# Relay_Board_1st_Iteration.net
KiCad netlist of a schematic drawn in EAGLE
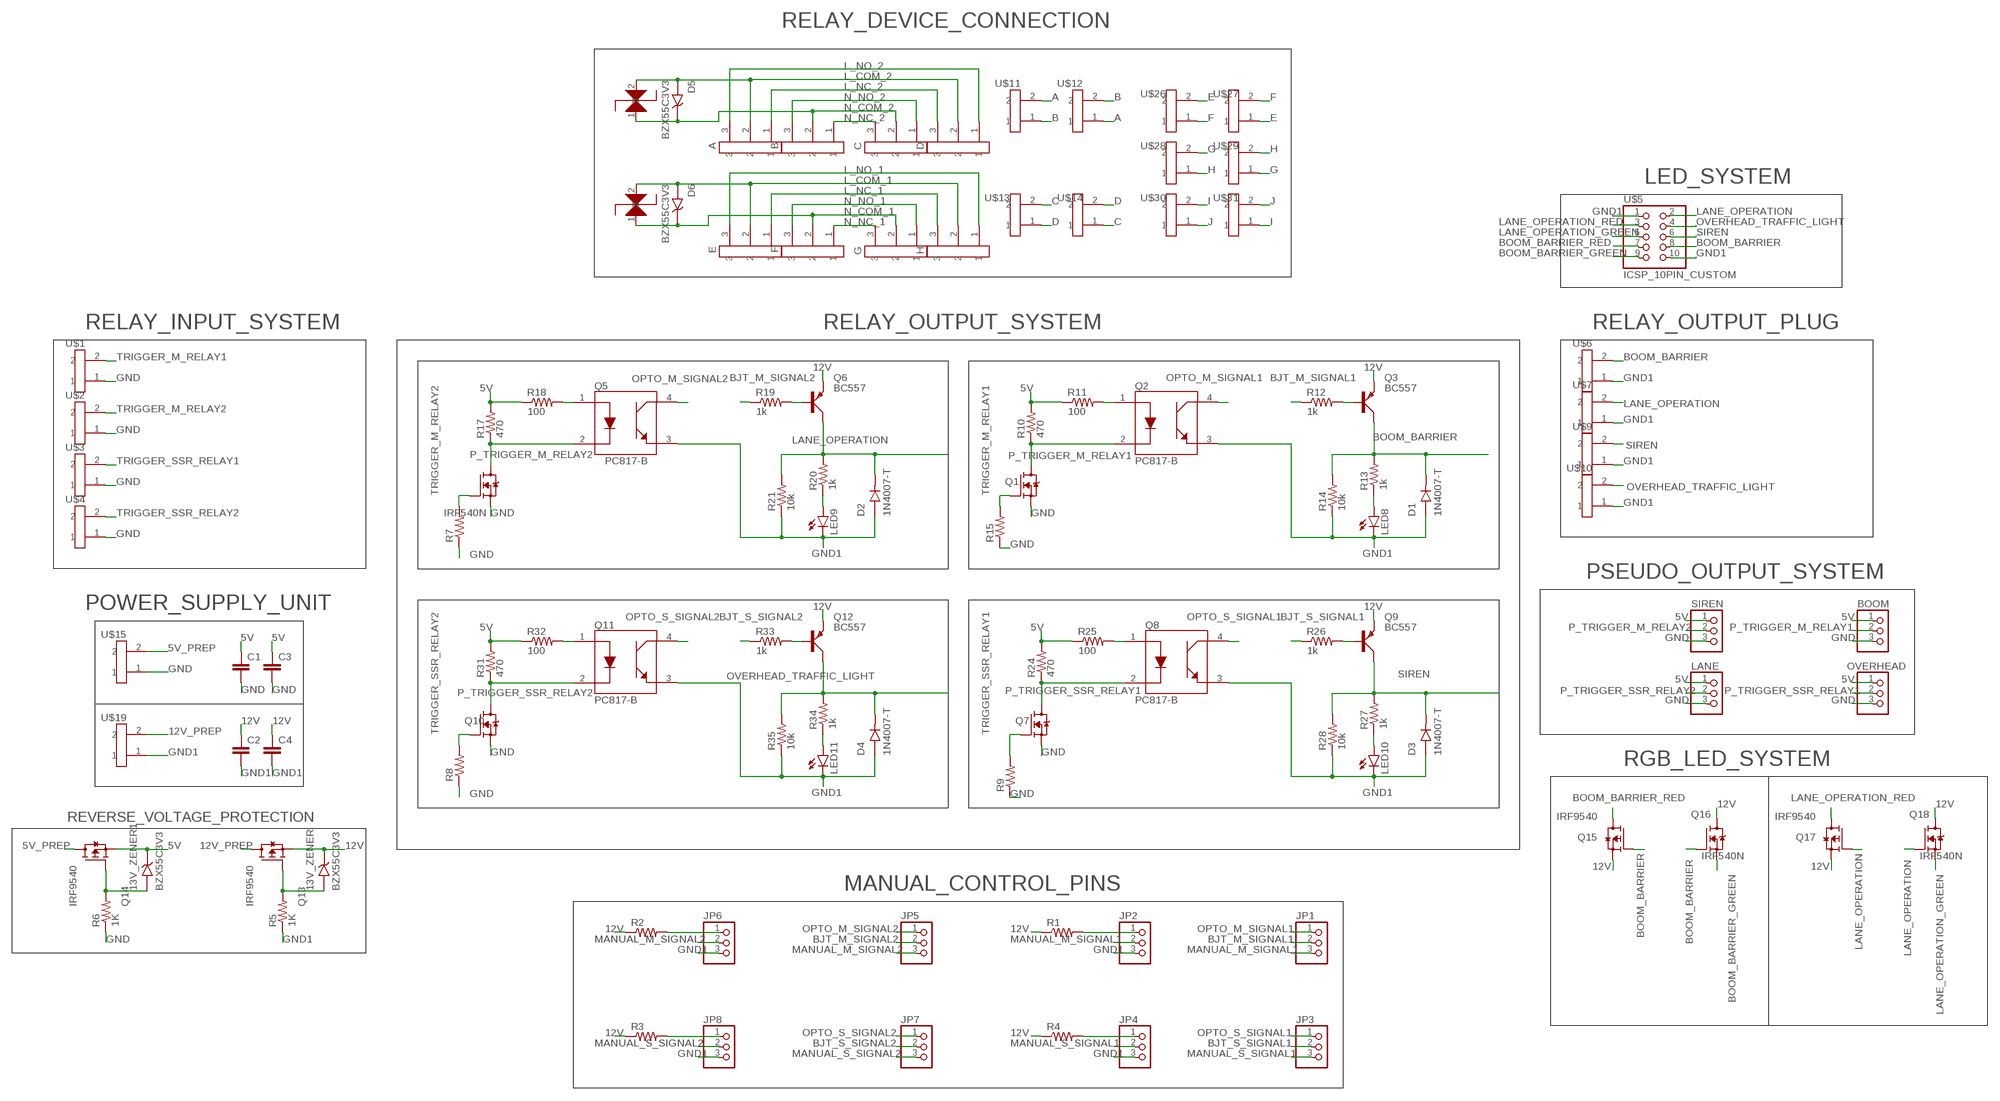
[diagram p0: schematic, sheet 1]

(export (version "E")
  (design (tool "Eeschema 10.0.6"))
  (components
    (comp (ref "13V_ZENER")
      (value "BZX55C3V3")
      (footprint "eagle-import:DIOAD928W47L399D179")
      (fields (field (name "MF") "Vishay Semiconductor") (field (name "MP") "BZX55C3V3-TR"))
      (libsource (lib "eagle-import") (part "BZX55C3V3"))
    )
    (comp (ref "13V_ZENER1")
      (value "BZX55C3V3")
      (footprint "eagle-import:DIOAD928W47L399D179")
      (fields (field (name "MF") "Vishay Semiconductor") (field (name "MP") "BZX55C3V3-TR"))
      (libsource (lib "eagle-import") (part "BZX55C3V3"))
    )
    (comp (ref "A")
      (value "GREEN_PLUG_90_3")
      (footprint "eagle-import:GREEN_PLUG_90_3")
      (libsource (lib "eagle-import") (part "GREEN_PLUG_90_3"))
    )
    (comp (ref "B")
      (value "GREEN_PLUG_90_3")
      (footprint "eagle-import:GREEN_PLUG_90_3")
      (libsource (lib "eagle-import") (part "GREEN_PLUG_90_3"))
    )
    (comp (ref "BOOM")
      (value "PINHD-1X3")
      (footprint "eagle-import:1X03")
      (libsource (lib "eagle-import") (part "PINHD-1X3"))
    )
    (comp (ref "C")
      (value "GREEN_PLUG_90_3")
      (footprint "eagle-import:GREEN_PLUG_90_3")
      (libsource (lib "eagle-import") (part "GREEN_PLUG_90_3"))
    )
    (comp (ref "C1")
      (value "CAPACITOR")
      (footprint "eagle-import:CAPACITOR")
      (libsource (lib "eagle-import") (part "CAPACITOR"))
    )
    (comp (ref "C2")
      (value "CAPACITOR")
      (footprint "eagle-import:CAPACITOR")
      (libsource (lib "eagle-import") (part "CAPACITOR"))
    )
    (comp (ref "C3")
      (value "CAPACITOR")
      (footprint "eagle-import:CAPACITOR")
      (libsource (lib "eagle-import") (part "CAPACITOR"))
    )
    (comp (ref "C4")
      (value "CAPACITOR")
      (footprint "eagle-import:CAPACITOR")
      (libsource (lib "eagle-import") (part "CAPACITOR"))
    )
    (comp (ref "D")
      (value "GREEN_PLUG_90_3")
      (footprint "eagle-import:GREEN_PLUG_90_3")
      (libsource (lib "eagle-import") (part "GREEN_PLUG_90_3"))
    )
    (comp (ref "D1")
      (value "1N4007-T")
      (footprint "eagle-import:DIOAD780W78L463D236")
      (fields (field (name "MF") "Diodes Incorporated"))
      (libsource (lib "eagle-import") (part "1N4007-T"))
    )
    (comp (ref "D2")
      (value "1N4007-T")
      (footprint "eagle-import:DIOAD780W78L463D236")
      (fields (field (name "MF") "Diodes Incorporated"))
      (libsource (lib "eagle-import") (part "1N4007-T"))
    )
    (comp (ref "D3")
      (value "1N4007-T")
      (footprint "eagle-import:DIOAD780W78L463D236")
      (fields (field (name "MF") "Diodes Incorporated"))
      (libsource (lib "eagle-import") (part "1N4007-T"))
    )
    (comp (ref "D4")
      (value "1N4007-T")
      (footprint "eagle-import:DIOAD780W78L463D236")
      (fields (field (name "MF") "Diodes Incorporated"))
      (libsource (lib "eagle-import") (part "1N4007-T"))
    )
    (comp (ref "D5")
      (value "BZX55C3V3")
      (footprint "eagle-import:DIOAD928W47L399D179")
      (fields (field (name "MF") "Vishay Semiconductor") (field (name "MP") "BZX55C3V3-TR"))
      (libsource (lib "eagle-import") (part "BZX55C3V3"))
    )
    (comp (ref "D6")
      (value "BZX55C3V3")
      (footprint "eagle-import:DIOAD928W47L399D179")
      (fields (field (name "MF") "Vishay Semiconductor") (field (name "MP") "BZX55C3V3-TR"))
      (libsource (lib "eagle-import") (part "BZX55C3V3"))
    )
    (comp (ref "E")
      (value "GREEN_PLUG_90_3")
      (footprint "eagle-import:GREEN_PLUG_90_3")
      (libsource (lib "eagle-import") (part "GREEN_PLUG_90_3"))
    )
    (comp (ref "F")
      (value "GREEN_PLUG_90_3")
      (footprint "eagle-import:GREEN_PLUG_90_3")
      (libsource (lib "eagle-import") (part "GREEN_PLUG_90_3"))
    )
    (comp (ref "G")
      (value "GREEN_PLUG_90_3")
      (footprint "eagle-import:GREEN_PLUG_90_3")
      (libsource (lib "eagle-import") (part "GREEN_PLUG_90_3"))
    )
    (comp (ref "H")
      (value "GREEN_PLUG_90_3")
      (footprint "eagle-import:GREEN_PLUG_90_3")
      (libsource (lib "eagle-import") (part "GREEN_PLUG_90_3"))
    )
    (comp (ref "JP1")
      (value "PINHD-1X3")
      (footprint "eagle-import:1X03")
      (libsource (lib "eagle-import") (part "PINHD-1X3"))
    )
    (comp (ref "JP2")
      (value "PINHD-1X3")
      (footprint "eagle-import:1X03")
      (libsource (lib "eagle-import") (part "PINHD-1X3"))
    )
    (comp (ref "JP3")
      (value "PINHD-1X3")
      (footprint "eagle-import:1X03")
      (libsource (lib "eagle-import") (part "PINHD-1X3"))
    )
    (comp (ref "JP4")
      (value "PINHD-1X3")
      (footprint "eagle-import:1X03")
      (libsource (lib "eagle-import") (part "PINHD-1X3"))
    )
    (comp (ref "JP5")
      (value "PINHD-1X3")
      (footprint "eagle-import:1X03")
      (libsource (lib "eagle-import") (part "PINHD-1X3"))
    )
    (comp (ref "JP6")
      (value "PINHD-1X3")
      (footprint "eagle-import:1X03")
      (libsource (lib "eagle-import") (part "PINHD-1X3"))
    )
    (comp (ref "JP7")
      (value "PINHD-1X3")
      (footprint "eagle-import:1X03")
      (libsource (lib "eagle-import") (part "PINHD-1X3"))
    )
    (comp (ref "JP8")
      (value "PINHD-1X3")
      (footprint "eagle-import:1X03")
      (libsource (lib "eagle-import") (part "PINHD-1X3"))
    )
    (comp (ref "LANE")
      (value "PINHD-1X3")
      (footprint "eagle-import:1X03")
      (libsource (lib "eagle-import") (part "PINHD-1X3"))
    )
    (comp (ref "LED8")
      (value "LED")
      (footprint "eagle-import:LED")
      (libsource (lib "eagle-import") (part "LED"))
    )
    (comp (ref "LED9")
      (value "LED")
      (footprint "eagle-import:LED")
      (libsource (lib "eagle-import") (part "LED"))
    )
    (comp (ref "LED10")
      (value "LED")
      (footprint "eagle-import:LED")
      (libsource (lib "eagle-import") (part "LED"))
    )
    (comp (ref "LED11")
      (value "LED")
      (footprint "eagle-import:LED")
      (libsource (lib "eagle-import") (part "LED"))
    )
    (comp (ref "OVERHEAD")
      (value "PINHD-1X3")
      (footprint "eagle-import:1X03")
      (libsource (lib "eagle-import") (part "PINHD-1X3"))
    )
    (comp (ref "Q1")
      (value "IRF540N")
      (footprint "eagle-import:TO254P1054X469X1930-3")
      (fields (field (name "MF") "Infineon Technologies"))
      (libsource (lib "eagle-import") (part "IRF540N"))
    )
    (comp (ref "Q2")
      (value "PC817-B")
      (footprint "eagle-import:DIP762W50P254L650H455Q4B")
      (fields (field (name "MF") "American Bright"))
      (libsource (lib "eagle-import") (part "PC817-B"))
    )
    (comp (ref "Q3")
      (value "BC557")
      (footprint "eagle-import:SOT54A")
      (fields (field (name "MF") "ON Semiconductor"))
      (libsource (lib "eagle-import") (part "BC557"))
    )
    (comp (ref "Q4")
      (value "IRF540N")
      (footprint "eagle-import:TO254P1054X469X1930-3")
      (fields (field (name "MF") "Infineon Technologies"))
      (libsource (lib "eagle-import") (part "IRF540N"))
    )
    (comp (ref "Q5")
      (value "PC817-B")
      (footprint "eagle-import:DIP762W50P254L650H455Q4B")
      (fields (field (name "MF") "American Bright"))
      (libsource (lib "eagle-import") (part "PC817-B"))
    )
    (comp (ref "Q6")
      (value "BC557")
      (footprint "eagle-import:SOT54A")
      (fields (field (name "MF") "ON Semiconductor"))
      (libsource (lib "eagle-import") (part "BC557"))
    )
    (comp (ref "Q7")
      (value "IRF540N")
      (footprint "eagle-import:TO254P1054X469X1930-3")
      (fields (field (name "MF") "Infineon Technologies"))
      (libsource (lib "eagle-import") (part "IRF540N"))
    )
    (comp (ref "Q8")
      (value "PC817-B")
      (footprint "eagle-import:DIP762W50P254L650H455Q4B")
      (fields (field (name "MF") "American Bright"))
      (libsource (lib "eagle-import") (part "PC817-B"))
    )
    (comp (ref "Q9")
      (value "BC557")
      (footprint "eagle-import:SOT54A")
      (fields (field (name "MF") "ON Semiconductor"))
      (libsource (lib "eagle-import") (part "BC557"))
    )
    (comp (ref "Q10")
      (value "IRF540N")
      (footprint "eagle-import:TO254P1054X469X1930-3")
      (fields (field (name "MF") "Infineon Technologies"))
      (libsource (lib "eagle-import") (part "IRF540N"))
    )
    (comp (ref "Q11")
      (value "PC817-B")
      (footprint "eagle-import:DIP762W50P254L650H455Q4B")
      (fields (field (name "MF") "American Bright"))
      (libsource (lib "eagle-import") (part "PC817-B"))
    )
    (comp (ref "Q12")
      (value "BC557")
      (footprint "eagle-import:SOT54A")
      (fields (field (name "MF") "ON Semiconductor"))
      (libsource (lib "eagle-import") (part "BC557"))
    )
    (comp (ref "Q13")
      (value "IRF9540")
      (footprint "eagle-import:TO254P1052X465X1989-3")
      (fields (field (name "MF") "Vishay Siliconix"))
      (libsource (lib "eagle-import") (part "IRF9540"))
    )
    (comp (ref "Q14")
      (value "IRF9540")
      (footprint "eagle-import:TO254P1052X465X1989-3")
      (fields (field (name "MF") "Vishay Siliconix"))
      (libsource (lib "eagle-import") (part "IRF9540"))
    )
    (comp (ref "Q15")
      (value "IRF9540")
      (footprint "eagle-import:TO254P1052X465X1989-3")
      (fields (field (name "MF") "Vishay Siliconix"))
      (libsource (lib "eagle-import") (part "IRF9540"))
    )
    (comp (ref "Q16")
      (value "IRF540N")
      (footprint "eagle-import:TO254P1054X469X1930-3")
      (fields (field (name "MF") "Infineon Technologies"))
      (libsource (lib "eagle-import") (part "IRF540N"))
    )
    (comp (ref "Q17")
      (value "IRF9540")
      (footprint "eagle-import:TO254P1052X465X1989-3")
      (fields (field (name "MF") "Vishay Siliconix"))
      (libsource (lib "eagle-import") (part "IRF9540"))
    )
    (comp (ref "Q18")
      (value "IRF540N")
      (footprint "eagle-import:TO254P1054X469X1930-3")
      (fields (field (name "MF") "Infineon Technologies"))
      (libsource (lib "eagle-import") (part "IRF540N"))
    )
    (comp (ref "R1")
      (value "RESISTOR")
      (footprint "eagle-import:RESISTOR")
      (libsource (lib "eagle-import") (part "RESISTOR"))
    )
    (comp (ref "R2")
      (value "RESISTOR")
      (footprint "eagle-import:RESISTOR")
      (libsource (lib "eagle-import") (part "RESISTOR"))
    )
    (comp (ref "R3")
      (value "RESISTOR")
      (footprint "eagle-import:RESISTOR")
      (libsource (lib "eagle-import") (part "RESISTOR"))
    )
    (comp (ref "R4")
      (value "RESISTOR")
      (footprint "eagle-import:RESISTOR")
      (libsource (lib "eagle-import") (part "RESISTOR"))
    )
    (comp (ref "R5")
      (value "1K")
      (footprint "eagle-import:RESISTOR")
      (libsource (lib "eagle-import") (part "RESISTOR"))
    )
    (comp (ref "R6")
      (value "1K")
      (footprint "eagle-import:RESISTOR")
      (libsource (lib "eagle-import") (part "RESISTOR"))
    )
    (comp (ref "R7")
      (value "RESISTOR")
      (footprint "eagle-import:RESISTOR")
      (libsource (lib "eagle-import") (part "RESISTOR"))
    )
    (comp (ref "R8")
      (value "RESISTOR")
      (footprint "eagle-import:RESISTOR")
      (libsource (lib "eagle-import") (part "RESISTOR"))
    )
    (comp (ref "R9")
      (value "RESISTOR")
      (footprint "eagle-import:RESISTOR")
      (libsource (lib "eagle-import") (part "RESISTOR"))
    )
    (comp (ref "R10")
      (value "470")
      (footprint "eagle-import:RESISTOR")
      (libsource (lib "eagle-import") (part "RESISTOR"))
    )
    (comp (ref "R11")
      (value "100")
      (footprint "eagle-import:RESISTOR")
      (libsource (lib "eagle-import") (part "RESISTOR"))
    )
    (comp (ref "R12")
      (value "1k")
      (footprint "eagle-import:RESISTOR")
      (libsource (lib "eagle-import") (part "RESISTOR"))
    )
    (comp (ref "R13")
      (value "1k")
      (footprint "eagle-import:RESISTOR")
      (libsource (lib "eagle-import") (part "RESISTOR"))
    )
    (comp (ref "R14")
      (value "10k")
      (footprint "eagle-import:RESISTOR")
      (libsource (lib "eagle-import") (part "RESISTOR"))
    )
    (comp (ref "R15")
      (value "RESISTOR")
      (footprint "eagle-import:RESISTOR")
      (libsource (lib "eagle-import") (part "RESISTOR"))
    )
    (comp (ref "R17")
      (value "470")
      (footprint "eagle-import:RESISTOR")
      (libsource (lib "eagle-import") (part "RESISTOR"))
    )
    (comp (ref "R18")
      (value "100")
      (footprint "eagle-import:RESISTOR")
      (libsource (lib "eagle-import") (part "RESISTOR"))
    )
    (comp (ref "R19")
      (value "1k")
      (footprint "eagle-import:RESISTOR")
      (libsource (lib "eagle-import") (part "RESISTOR"))
    )
    (comp (ref "R20")
      (value "1k")
      (footprint "eagle-import:RESISTOR")
      (libsource (lib "eagle-import") (part "RESISTOR"))
    )
    (comp (ref "R21")
      (value "10k")
      (footprint "eagle-import:RESISTOR")
      (libsource (lib "eagle-import") (part "RESISTOR"))
    )
    (comp (ref "R24")
      (value "470")
      (footprint "eagle-import:RESISTOR")
      (libsource (lib "eagle-import") (part "RESISTOR"))
    )
    (comp (ref "R25")
      (value "100")
      (footprint "eagle-import:RESISTOR")
      (libsource (lib "eagle-import") (part "RESISTOR"))
    )
    (comp (ref "R26")
      (value "1k")
      (footprint "eagle-import:RESISTOR")
      (libsource (lib "eagle-import") (part "RESISTOR"))
    )
    (comp (ref "R27")
      (value "1k")
      (footprint "eagle-import:RESISTOR")
      (libsource (lib "eagle-import") (part "RESISTOR"))
    )
    (comp (ref "R28")
      (value "10k")
      (footprint "eagle-import:RESISTOR")
      (libsource (lib "eagle-import") (part "RESISTOR"))
    )
    (comp (ref "R31")
      (value "470")
      (footprint "eagle-import:RESISTOR")
      (libsource (lib "eagle-import") (part "RESISTOR"))
    )
    (comp (ref "R32")
      (value "100")
      (footprint "eagle-import:RESISTOR")
      (libsource (lib "eagle-import") (part "RESISTOR"))
    )
    (comp (ref "R33")
      (value "1k")
      (footprint "eagle-import:RESISTOR")
      (libsource (lib "eagle-import") (part "RESISTOR"))
    )
    (comp (ref "R34")
      (value "1k")
      (footprint "eagle-import:RESISTOR")
      (libsource (lib "eagle-import") (part "RESISTOR"))
    )
    (comp (ref "R35")
      (value "10k")
      (footprint "eagle-import:RESISTOR")
      (libsource (lib "eagle-import") (part "RESISTOR"))
    )
    (comp (ref "SIREN")
      (value "PINHD-1X3")
      (footprint "eagle-import:1X03")
      (libsource (lib "eagle-import") (part "PINHD-1X3"))
    )
    (comp (ref "U$1")
      (value "GREEN_PLUG_90_2")
      (footprint "eagle-import:GREEN_PLUG_90_2")
      (libsource (lib "eagle-import") (part "GREEN_PLUG_90_2"))
    )
    (comp (ref "U$2")
      (value "GREEN_PLUG_90_2")
      (footprint "eagle-import:GREEN_PLUG_90_2")
      (libsource (lib "eagle-import") (part "GREEN_PLUG_90_2"))
    )
    (comp (ref "U$3")
      (value "GREEN_PLUG_90_2")
      (footprint "eagle-import:GREEN_PLUG_90_2")
      (libsource (lib "eagle-import") (part "GREEN_PLUG_90_2"))
    )
    (comp (ref "U$4")
      (value "GREEN_PLUG_90_2")
      (footprint "eagle-import:GREEN_PLUG_90_2")
      (libsource (lib "eagle-import") (part "GREEN_PLUG_90_2"))
    )
    (comp (ref "U$5")
      (value "ICSP_10PIN_CUSTOM")
      (footprint "eagle-import:ICSP_10PIN_CUSTOM")
      (libsource (lib "eagle-import") (part "ICSP_10PIN_CUSTOM"))
    )
    (comp (ref "U$6")
      (value "GREEN_PLUG_90_2")
      (footprint "eagle-import:GREEN_PLUG_90_2")
      (libsource (lib "eagle-import") (part "GREEN_PLUG_90_2"))
    )
    (comp (ref "U$7")
      (value "GREEN_PLUG_90_2")
      (footprint "eagle-import:GREEN_PLUG_90_2")
      (libsource (lib "eagle-import") (part "GREEN_PLUG_90_2"))
    )
    (comp (ref "U$9")
      (value "GREEN_PLUG_90_2")
      (footprint "eagle-import:GREEN_PLUG_90_2")
      (libsource (lib "eagle-import") (part "GREEN_PLUG_90_2"))
    )
    (comp (ref "U$10")
      (value "GREEN_PLUG_90_2")
      (footprint "eagle-import:GREEN_PLUG_90_2")
      (libsource (lib "eagle-import") (part "GREEN_PLUG_90_2"))
    )
    (comp (ref "U$11")
      (value "GREEN_PLUG_90_2")
      (footprint "eagle-import:GREEN_PLUG_90_2")
      (libsource (lib "eagle-import") (part "GREEN_PLUG_90_2"))
    )
    (comp (ref "U$12")
      (value "GREEN_PLUG_90_2")
      (footprint "eagle-import:GREEN_PLUG_90_2")
      (libsource (lib "eagle-import") (part "GREEN_PLUG_90_2"))
    )
    (comp (ref "U$13")
      (value "GREEN_PLUG_90_2")
      (footprint "eagle-import:GREEN_PLUG_90_2")
      (libsource (lib "eagle-import") (part "GREEN_PLUG_90_2"))
    )
    (comp (ref "U$14")
      (value "GREEN_PLUG_90_2")
      (footprint "eagle-import:GREEN_PLUG_90_2")
      (libsource (lib "eagle-import") (part "GREEN_PLUG_90_2"))
    )
    (comp (ref "U$15")
      (value "GREEN_PLUG_90_2")
      (footprint "eagle-import:GREEN_PLUG_90_2")
      (libsource (lib "eagle-import") (part "GREEN_PLUG_90_2"))
    )
    (comp (ref "U$19")
      (value "GREEN_PLUG_90_2")
      (footprint "eagle-import:GREEN_PLUG_90_2")
      (libsource (lib "eagle-import") (part "GREEN_PLUG_90_2"))
    )
    (comp (ref "U$24")
      (value "1KE100A_CUSTOM")
      (footprint "eagle-import:1KE100A_CUSTOM")
      (libsource (lib "eagle-import") (part "1KE100A_CUSTOM"))
    )
    (comp (ref "U$25")
      (value "1KE100A_CUSTOM")
      (footprint "eagle-import:1KE100A_CUSTOM")
      (libsource (lib "eagle-import") (part "1KE100A_CUSTOM"))
    )
    (comp (ref "U$26")
      (value "GREEN_PLUG_90_2")
      (footprint "eagle-import:GREEN_PLUG_90_2")
      (libsource (lib "eagle-import") (part "GREEN_PLUG_90_2"))
    )
    (comp (ref "U$27")
      (value "GREEN_PLUG_90_2")
      (footprint "eagle-import:GREEN_PLUG_90_2")
      (libsource (lib "eagle-import") (part "GREEN_PLUG_90_2"))
    )
    (comp (ref "U$28")
      (value "GREEN_PLUG_90_2")
      (footprint "eagle-import:GREEN_PLUG_90_2")
      (libsource (lib "eagle-import") (part "GREEN_PLUG_90_2"))
    )
    (comp (ref "U$29")
      (value "GREEN_PLUG_90_2")
      (footprint "eagle-import:GREEN_PLUG_90_2")
      (libsource (lib "eagle-import") (part "GREEN_PLUG_90_2"))
    )
    (comp (ref "U$30")
      (value "GREEN_PLUG_90_2")
      (footprint "eagle-import:GREEN_PLUG_90_2")
      (libsource (lib "eagle-import") (part "GREEN_PLUG_90_2"))
    )
    (comp (ref "U$31")
      (value "GREEN_PLUG_90_2")
      (footprint "eagle-import:GREEN_PLUG_90_2")
      (libsource (lib "eagle-import") (part "GREEN_PLUG_90_2"))
    )
  )
  (nets
    (net (code "1") (name "/5V") (class "Default")
      (node (ref "13V_ZENER1") (pin "C") (pinfunction "K_C") (pintype "passive"))
      (node (ref "BOOM") (pin "1") (pinfunction "1_1") (pintype "passive"))
      (node (ref "C1") (pin "1") (pinfunction "1_1") (pintype "passive"))
      (node (ref "C3") (pin "1") (pinfunction "1_1") (pintype "passive"))
      (node (ref "LANE") (pin "1") (pinfunction "1_1") (pintype "passive"))
      (node (ref "OVERHEAD") (pin "1") (pinfunction "1_1") (pintype "passive"))
      (node (ref "Q14") (pin "3") (pinfunction "S_3") (pintype "passive"))
      (node (ref "R10") (pin "2") (pinfunction "2_2") (pintype "passive"))
      (node (ref "R11") (pin "1") (pinfunction "1_1") (pintype "passive"))
      (node (ref "R17") (pin "2") (pinfunction "2_2") (pintype "passive"))
      (node (ref "R18") (pin "1") (pinfunction "1_1") (pintype "passive"))
      (node (ref "R24") (pin "2") (pinfunction "2_2") (pintype "passive"))
      (node (ref "R25") (pin "1") (pinfunction "1_1") (pintype "passive"))
      (node (ref "R31") (pin "2") (pinfunction "2_2") (pintype "passive"))
      (node (ref "R32") (pin "1") (pinfunction "1_1") (pintype "passive"))
      (node (ref "SIREN") (pin "1") (pinfunction "1_1") (pintype "passive"))
    )
    (net (code "2") (name "/5V_PREP") (class "Default")
      (node (ref "Q14") (pin "2") (pinfunction "D_2") (pintype "passive"))
      (node (ref "U$15") (pin "2") (pinfunction "2_2") (pintype "passive"))
    )
    (net (code "3") (name "/12V") (class "Default")
      (node (ref "13V_ZENER") (pin "C") (pinfunction "K_C") (pintype "passive"))
      (node (ref "C2") (pin "1") (pinfunction "1_1") (pintype "passive"))
      (node (ref "C4") (pin "1") (pinfunction "1_1") (pintype "passive"))
      (node (ref "Q12") (pin "E") (pinfunction "E_E") (pintype "passive"))
      (node (ref "Q13") (pin "3") (pinfunction "S_3") (pintype "passive"))
      (node (ref "Q15") (pin "3") (pinfunction "S_3") (pintype "passive"))
      (node (ref "Q16") (pin "2") (pinfunction "D_2") (pintype "passive"))
      (node (ref "Q17") (pin "3") (pinfunction "S_3") (pintype "passive"))
      (node (ref "Q18") (pin "2") (pinfunction "D_2") (pintype "passive"))
      (node (ref "Q3") (pin "E") (pinfunction "E_E") (pintype "passive"))
      (node (ref "Q6") (pin "E") (pinfunction "E_E") (pintype "passive"))
      (node (ref "Q9") (pin "E") (pinfunction "E_E") (pintype "passive"))
      (node (ref "R1") (pin "1") (pinfunction "1_1") (pintype "passive"))
      (node (ref "R2") (pin "1") (pinfunction "1_1") (pintype "passive"))
      (node (ref "R3") (pin "1") (pinfunction "1_1") (pintype "passive"))
      (node (ref "R4") (pin "1") (pinfunction "1_1") (pintype "passive"))
    )
    (net (code "4") (name "/12V_PREP") (class "Default")
      (node (ref "Q13") (pin "2") (pinfunction "D_2") (pintype "passive"))
      (node (ref "U$19") (pin "2") (pinfunction "2_2") (pintype "passive"))
    )
    (net (code "5") (name "/A") (class "Default")
      (node (ref "U$11") (pin "2") (pinfunction "2_2") (pintype "passive"))
      (node (ref "U$12") (pin "1") (pinfunction "1_1") (pintype "passive"))
    )
    (net (code "6") (name "/B") (class "Default")
      (node (ref "U$11") (pin "1") (pinfunction "1_1") (pintype "passive"))
      (node (ref "U$12") (pin "2") (pinfunction "2_2") (pintype "passive"))
    )
    (net (code "7") (name "/BJT_M_SIGNAL1") (class "Default")
      (node (ref "JP1") (pin "2") (pinfunction "2_2") (pintype "passive"))
      (node (ref "R12") (pin "1") (pinfunction "1_1") (pintype "passive"))
    )
    (net (code "8") (name "/BJT_M_SIGNAL2") (class "Default")
      (node (ref "JP5") (pin "2") (pinfunction "2_2") (pintype "passive"))
      (node (ref "R19") (pin "1") (pinfunction "1_1") (pintype "passive"))
    )
    (net (code "9") (name "/BJT_S_SIGNAL1") (class "Default")
      (node (ref "JP3") (pin "2") (pinfunction "2_2") (pintype "passive"))
      (node (ref "R26") (pin "1") (pinfunction "1_1") (pintype "passive"))
    )
    (net (code "10") (name "/BJT_S_SIGNAL2") (class "Default")
      (node (ref "JP7") (pin "2") (pinfunction "2_2") (pintype "passive"))
      (node (ref "R33") (pin "1") (pinfunction "1_1") (pintype "passive"))
    )
    (net (code "11") (name "/BOOM_BARRIER") (class "Default")
      (node (ref "D1") (pin "K") (pinfunction "K_K") (pintype "passive"))
      (node (ref "Q15") (pin "1") (pinfunction "G_1") (pintype "passive"))
      (node (ref "Q16") (pin "1") (pinfunction "G_1") (pintype "passive"))
      (node (ref "Q3") (pin "C") (pinfunction "C_C") (pintype "passive"))
      (node (ref "R13") (pin "2") (pinfunction "2_2") (pintype "passive"))
      (node (ref "R14") (pin "2") (pinfunction "2_2") (pintype "passive"))
      (node (ref "U$5") (pin "8") (pinfunction "8_8") (pintype "passive"))
      (node (ref "U$6") (pin "2") (pinfunction "2_2") (pintype "passive"))
    )
    (net (code "12") (name "/BOOM_BARRIER_GREEN") (class "Default")
      (node (ref "Q16") (pin "3") (pinfunction "S_3") (pintype "passive"))
      (node (ref "U$5") (pin "9") (pinfunction "9_9") (pintype "passive"))
    )
    (net (code "13") (name "/BOOM_BARRIER_RED") (class "Default")
      (node (ref "Q15") (pin "2") (pinfunction "D_2") (pintype "passive"))
      (node (ref "U$5") (pin "7") (pinfunction "7_7") (pintype "passive"))
    )
    (net (code "14") (name "/C") (class "Default")
      (node (ref "U$13") (pin "2") (pinfunction "2_2") (pintype "passive"))
      (node (ref "U$14") (pin "1") (pinfunction "1_1") (pintype "passive"))
    )
    (net (code "15") (name "/D") (class "Default")
      (node (ref "U$13") (pin "1") (pinfunction "1_1") (pintype "passive"))
      (node (ref "U$14") (pin "2") (pinfunction "2_2") (pintype "passive"))
    )
    (net (code "16") (name "/E") (class "Default")
      (node (ref "U$26") (pin "2") (pinfunction "2_2") (pintype "passive"))
      (node (ref "U$27") (pin "1") (pinfunction "1_1") (pintype "passive"))
    )
    (net (code "17") (name "/F") (class "Default")
      (node (ref "U$26") (pin "1") (pinfunction "1_1") (pintype "passive"))
      (node (ref "U$27") (pin "2") (pinfunction "2_2") (pintype "passive"))
    )
    (net (code "18") (name "/G") (class "Default")
      (node (ref "U$28") (pin "2") (pinfunction "2_2") (pintype "passive"))
      (node (ref "U$29") (pin "1") (pinfunction "1_1") (pintype "passive"))
    )
    (net (code "19") (name "/GND") (class "Default")
      (node (ref "BOOM") (pin "3") (pinfunction "3_3") (pintype "passive"))
      (node (ref "C1") (pin "2") (pinfunction "2_2") (pintype "passive"))
      (node (ref "C3") (pin "2") (pinfunction "2_2") (pintype "passive"))
      (node (ref "LANE") (pin "3") (pinfunction "3_3") (pintype "passive"))
      (node (ref "OVERHEAD") (pin "3") (pinfunction "3_3") (pintype "passive"))
      (node (ref "Q1") (pin "3") (pinfunction "S_3") (pintype "passive"))
      (node (ref "Q10") (pin "3") (pinfunction "S_3") (pintype "passive"))
      (node (ref "Q4") (pin "3") (pinfunction "S_3") (pintype "passive"))
      (node (ref "Q7") (pin "3") (pinfunction "S_3") (pintype "passive"))
      (node (ref "R15") (pin "1") (pinfunction "1_1") (pintype "passive"))
      (node (ref "R6") (pin "1") (pinfunction "1_1") (pintype "passive"))
      (node (ref "R7") (pin "1") (pinfunction "1_1") (pintype "passive"))
      (node (ref "R8") (pin "1") (pinfunction "1_1") (pintype "passive"))
      (node (ref "R9") (pin "1") (pinfunction "1_1") (pintype "passive"))
      (node (ref "SIREN") (pin "3") (pinfunction "3_3") (pintype "passive"))
      (node (ref "U$1") (pin "1") (pinfunction "1_1") (pintype "passive"))
      (node (ref "U$15") (pin "1") (pinfunction "1_1") (pintype "passive"))
      (node (ref "U$2") (pin "1") (pinfunction "1_1") (pintype "passive"))
      (node (ref "U$3") (pin "1") (pinfunction "1_1") (pintype "passive"))
      (node (ref "U$4") (pin "1") (pinfunction "1_1") (pintype "passive"))
    )
    (net (code "20") (name "/GND1") (class "Default")
      (node (ref "C2") (pin "2") (pinfunction "2_2") (pintype "passive"))
      (node (ref "C4") (pin "2") (pinfunction "2_2") (pintype "passive"))
      (node (ref "D1") (pin "A") (pinfunction "A_A") (pintype "passive"))
      (node (ref "D2") (pin "A") (pinfunction "A_A") (pintype "passive"))
      (node (ref "D3") (pin "A") (pinfunction "A_A") (pintype "passive"))
      (node (ref "D4") (pin "A") (pinfunction "A_A") (pintype "passive"))
      (node (ref "JP2") (pin "3") (pinfunction "3_3") (pintype "passive"))
      (node (ref "JP4") (pin "3") (pinfunction "3_3") (pintype "passive"))
      (node (ref "JP6") (pin "3") (pinfunction "3_3") (pintype "passive"))
      (node (ref "JP8") (pin "3") (pinfunction "3_3") (pintype "passive"))
      (node (ref "LED10") (pin "K") (pinfunction "C_K") (pintype "passive"))
      (node (ref "LED11") (pin "K") (pinfunction "C_K") (pintype "passive"))
      (node (ref "LED8") (pin "K") (pinfunction "C_K") (pintype "passive"))
      (node (ref "LED9") (pin "K") (pinfunction "C_K") (pintype "passive"))
      (node (ref "Q11") (pin "3") (pinfunction "EMITTER_3") (pintype "passive"))
      (node (ref "Q2") (pin "3") (pinfunction "EMITTER_3") (pintype "passive"))
      (node (ref "Q5") (pin "3") (pinfunction "EMITTER_3") (pintype "passive"))
      (node (ref "Q8") (pin "3") (pinfunction "EMITTER_3") (pintype "passive"))
      (node (ref "R14") (pin "1") (pinfunction "1_1") (pintype "passive"))
      (node (ref "R21") (pin "1") (pinfunction "1_1") (pintype "passive"))
      (node (ref "R28") (pin "1") (pinfunction "1_1") (pintype "passive"))
      (node (ref "R35") (pin "1") (pinfunction "1_1") (pintype "passive"))
      (node (ref "R5") (pin "1") (pinfunction "1_1") (pintype "passive"))
      (node (ref "U$10") (pin "1") (pinfunction "1_1") (pintype "passive"))
      (node (ref "U$19") (pin "1") (pinfunction "1_1") (pintype "passive"))
      (node (ref "U$5") (pin "1") (pinfunction "1_1") (pintype "passive"))
      (node (ref "U$5") (pin "10") (pinfunction "10_10") (pintype "passive"))
      (node (ref "U$6") (pin "1") (pinfunction "1_1") (pintype "passive"))
      (node (ref "U$7") (pin "1") (pinfunction "1_1") (pintype "passive"))
      (node (ref "U$9") (pin "1") (pinfunction "1_1") (pintype "passive"))
    )
    (net (code "21") (name "/H") (class "Default")
      (node (ref "U$28") (pin "1") (pinfunction "1_1") (pintype "passive"))
      (node (ref "U$29") (pin "2") (pinfunction "2_2") (pintype "passive"))
    )
    (net (code "22") (name "/I") (class "Default")
      (node (ref "U$30") (pin "2") (pinfunction "2_2") (pintype "passive"))
      (node (ref "U$31") (pin "1") (pinfunction "1_1") (pintype "passive"))
    )
    (net (code "23") (name "/J") (class "Default")
      (node (ref "U$30") (pin "1") (pinfunction "1_1") (pintype "passive"))
      (node (ref "U$31") (pin "2") (pinfunction "2_2") (pintype "passive"))
    )
    (net (code "24") (name "/LANE_OPERATION") (class "Default")
      (node (ref "D2") (pin "K") (pinfunction "K_K") (pintype "passive"))
      (node (ref "Q17") (pin "1") (pinfunction "G_1") (pintype "passive"))
      (node (ref "Q18") (pin "1") (pinfunction "G_1") (pintype "passive"))
      (node (ref "Q6") (pin "C") (pinfunction "C_C") (pintype "passive"))
      (node (ref "R20") (pin "2") (pinfunction "2_2") (pintype "passive"))
      (node (ref "R21") (pin "2") (pinfunction "2_2") (pintype "passive"))
      (node (ref "U$5") (pin "2") (pinfunction "2_2") (pintype "passive"))
      (node (ref "U$7") (pin "2") (pinfunction "2_2") (pintype "passive"))
    )
    (net (code "25") (name "/LANE_OPERATION_GREEN") (class "Default")
      (node (ref "Q18") (pin "3") (pinfunction "S_3") (pintype "passive"))
      (node (ref "U$5") (pin "5") (pinfunction "5_5") (pintype "passive"))
    )
    (net (code "26") (name "/LANE_OPERATION_RED") (class "Default")
      (node (ref "Q17") (pin "2") (pinfunction "D_2") (pintype "passive"))
      (node (ref "U$5") (pin "3") (pinfunction "3_3") (pintype "passive"))
    )
    (net (code "27") (name "/L_COM_1") (class "Default")
      (node (ref "D6") (pin "A") (pinfunction "A_A") (pintype "passive"))
      (node (ref "E") (pin "2") (pinfunction "2_2") (pintype "passive"))
      (node (ref "H") (pin "2") (pinfunction "2_2") (pintype "passive"))
      (node (ref "U$25") (pin "2") (pinfunction "2_2") (pintype "bidirectional"))
    )
    (net (code "28") (name "/L_COM_2") (class "Default")
      (node (ref "A") (pin "2") (pinfunction "2_2") (pintype "passive"))
      (node (ref "D") (pin "2") (pinfunction "2_2") (pintype "passive"))
      (node (ref "D5") (pin "A") (pinfunction "A_A") (pintype "passive"))
      (node (ref "U$24") (pin "2") (pinfunction "2_2") (pintype "bidirectional"))
    )
    (net (code "29") (name "/L_NC_1") (class "Default")
      (node (ref "E") (pin "1") (pinfunction "1_1") (pintype "passive"))
      (node (ref "H") (pin "3") (pinfunction "3_3") (pintype "passive"))
    )
    (net (code "30") (name "/L_NC_2") (class "Default")
      (node (ref "A") (pin "1") (pinfunction "1_1") (pintype "passive"))
      (node (ref "D") (pin "3") (pinfunction "3_3") (pintype "passive"))
    )
    (net (code "31") (name "/L_NO_1") (class "Default")
      (node (ref "E") (pin "3") (pinfunction "3_3") (pintype "passive"))
      (node (ref "H") (pin "1") (pinfunction "1_1") (pintype "passive"))
    )
    (net (code "32") (name "/L_NO_2") (class "Default")
      (node (ref "A") (pin "3") (pinfunction "3_3") (pintype "passive"))
      (node (ref "D") (pin "1") (pinfunction "1_1") (pintype "passive"))
    )
    (net (code "33") (name "/MANUAL_M_SIGNAL1") (class "Default")
      (node (ref "JP1") (pin "3") (pinfunction "3_3") (pintype "passive"))
      (node (ref "JP2") (pin "2") (pinfunction "2_2") (pintype "passive"))
    )
    (net (code "34") (name "/MANUAL_M_SIGNAL2") (class "Default")
      (node (ref "JP5") (pin "3") (pinfunction "3_3") (pintype "passive"))
      (node (ref "JP6") (pin "2") (pinfunction "2_2") (pintype "passive"))
    )
    (net (code "35") (name "/MANUAL_S_SIGNAL1") (class "Default")
      (node (ref "JP3") (pin "3") (pinfunction "3_3") (pintype "passive"))
      (node (ref "JP4") (pin "2") (pinfunction "2_2") (pintype "passive"))
    )
    (net (code "36") (name "/MANUAL_S_SIGNAL2") (class "Default")
      (node (ref "JP7") (pin "3") (pinfunction "3_3") (pintype "passive"))
      (node (ref "JP8") (pin "2") (pinfunction "2_2") (pintype "passive"))
    )
    (net (code "37") (name "/N_COM_1") (class "Default")
      (node (ref "D6") (pin "C") (pinfunction "K_C") (pintype "passive"))
      (node (ref "F") (pin "2") (pinfunction "2_2") (pintype "passive"))
      (node (ref "G") (pin "2") (pinfunction "2_2") (pintype "passive"))
      (node (ref "U$25") (pin "1") (pinfunction "1_1") (pintype "bidirectional"))
    )
    (net (code "38") (name "/N_COM_2") (class "Default")
      (node (ref "B") (pin "2") (pinfunction "2_2") (pintype "passive"))
      (node (ref "C") (pin "2") (pinfunction "2_2") (pintype "passive"))
      (node (ref "D5") (pin "C") (pinfunction "K_C") (pintype "passive"))
      (node (ref "U$24") (pin "1") (pinfunction "1_1") (pintype "bidirectional"))
    )
    (net (code "39") (name "/N_NC_1") (class "Default")
      (node (ref "F") (pin "1") (pinfunction "1_1") (pintype "passive"))
      (node (ref "G") (pin "3") (pinfunction "3_3") (pintype "passive"))
    )
    (net (code "40") (name "/N_NC_2") (class "Default")
      (node (ref "B") (pin "1") (pinfunction "1_1") (pintype "passive"))
      (node (ref "C") (pin "3") (pinfunction "3_3") (pintype "passive"))
    )
    (net (code "41") (name "/N_NO_1") (class "Default")
      (node (ref "F") (pin "3") (pinfunction "3_3") (pintype "passive"))
      (node (ref "G") (pin "1") (pinfunction "1_1") (pintype "passive"))
    )
    (net (code "42") (name "/N_NO_2") (class "Default")
      (node (ref "B") (pin "3") (pinfunction "3_3") (pintype "passive"))
      (node (ref "C") (pin "1") (pinfunction "1_1") (pintype "passive"))
    )
    (net (code "43") (name "/OPTO_M_SIGNAL1") (class "Default")
      (node (ref "JP1") (pin "1") (pinfunction "1_1") (pintype "passive"))
      (node (ref "Q2") (pin "4") (pinfunction "COLLECTOR_4") (pintype "passive"))
    )
    (net (code "44") (name "/OPTO_M_SIGNAL2") (class "Default")
      (node (ref "JP5") (pin "1") (pinfunction "1_1") (pintype "passive"))
      (node (ref "Q5") (pin "4") (pinfunction "COLLECTOR_4") (pintype "passive"))
    )
    (net (code "45") (name "/OPTO_S_SIGNAL1") (class "Default")
      (node (ref "JP3") (pin "1") (pinfunction "1_1") (pintype "passive"))
      (node (ref "Q8") (pin "4") (pinfunction "COLLECTOR_4") (pintype "passive"))
    )
    (net (code "46") (name "/OPTO_S_SIGNAL2") (class "Default")
      (node (ref "JP7") (pin "1") (pinfunction "1_1") (pintype "passive"))
      (node (ref "Q11") (pin "4") (pinfunction "COLLECTOR_4") (pintype "passive"))
    )
    (net (code "47") (name "/OVERHEAD_TRAFFIC_LIGHT") (class "Default")
      (node (ref "D4") (pin "K") (pinfunction "K_K") (pintype "passive"))
      (node (ref "Q12") (pin "C") (pinfunction "C_C") (pintype "passive"))
      (node (ref "R34") (pin "2") (pinfunction "2_2") (pintype "passive"))
      (node (ref "R35") (pin "2") (pinfunction "2_2") (pintype "passive"))
      (node (ref "U$10") (pin "2") (pinfunction "2_2") (pintype "passive"))
      (node (ref "U$5") (pin "4") (pinfunction "4_4") (pintype "passive"))
    )
    (net (code "48") (name "/P_TRIGGER_M_RELAY1") (class "Default")
      (node (ref "BOOM") (pin "2") (pinfunction "2_2") (pintype "passive"))
      (node (ref "Q1") (pin "2") (pinfunction "D_2") (pintype "passive"))
      (node (ref "Q2") (pin "2") (pinfunction "CATHODE_2") (pintype "passive"))
      (node (ref "R10") (pin "1") (pinfunction "1_1") (pintype "passive"))
    )
    (net (code "49") (name "/P_TRIGGER_M_RELAY2") (class "Default")
      (node (ref "Q4") (pin "2") (pinfunction "D_2") (pintype "passive"))
      (node (ref "Q5") (pin "2") (pinfunction "CATHODE_2") (pintype "passive"))
      (node (ref "R17") (pin "1") (pinfunction "1_1") (pintype "passive"))
      (node (ref "SIREN") (pin "2") (pinfunction "2_2") (pintype "passive"))
    )
    (net (code "50") (name "/P_TRIGGER_SSR_RELAY1") (class "Default")
      (node (ref "OVERHEAD") (pin "2") (pinfunction "2_2") (pintype "passive"))
      (node (ref "Q7") (pin "2") (pinfunction "D_2") (pintype "passive"))
      (node (ref "Q8") (pin "2") (pinfunction "CATHODE_2") (pintype "passive"))
      (node (ref "R24") (pin "1") (pinfunction "1_1") (pintype "passive"))
    )
    (net (code "51") (name "/P_TRIGGER_SSR_RELAY2") (class "Default")
      (node (ref "LANE") (pin "2") (pinfunction "2_2") (pintype "passive"))
      (node (ref "Q10") (pin "2") (pinfunction "D_2") (pintype "passive"))
      (node (ref "Q11") (pin "2") (pinfunction "CATHODE_2") (pintype "passive"))
      (node (ref "R31") (pin "1") (pinfunction "1_1") (pintype "passive"))
    )
    (net (code "52") (name "/SIREN") (class "Default")
      (node (ref "D3") (pin "K") (pinfunction "K_K") (pintype "passive"))
      (node (ref "Q9") (pin "C") (pinfunction "C_C") (pintype "passive"))
      (node (ref "R27") (pin "2") (pinfunction "2_2") (pintype "passive"))
      (node (ref "R28") (pin "2") (pinfunction "2_2") (pintype "passive"))
      (node (ref "U$5") (pin "6") (pinfunction "6_6") (pintype "passive"))
      (node (ref "U$9") (pin "2") (pinfunction "2_2") (pintype "passive"))
    )
    (net (code "53") (name "/TRIGGER_M_RELAY1") (class "Default")
      (node (ref "Q1") (pin "1") (pinfunction "G_1") (pintype "passive"))
      (node (ref "R15") (pin "2") (pinfunction "2_2") (pintype "passive"))
      (node (ref "U$1") (pin "2") (pinfunction "2_2") (pintype "passive"))
    )
    (net (code "54") (name "/TRIGGER_M_RELAY2") (class "Default")
      (node (ref "Q4") (pin "1") (pinfunction "G_1") (pintype "passive"))
      (node (ref "R7") (pin "2") (pinfunction "2_2") (pintype "passive"))
      (node (ref "U$2") (pin "2") (pinfunction "2_2") (pintype "passive"))
    )
    (net (code "55") (name "/TRIGGER_SSR_RELAY1") (class "Default")
      (node (ref "Q7") (pin "1") (pinfunction "G_1") (pintype "passive"))
      (node (ref "R9") (pin "2") (pinfunction "2_2") (pintype "passive"))
      (node (ref "U$3") (pin "2") (pinfunction "2_2") (pintype "passive"))
    )
    (net (code "56") (name "/TRIGGER_SSR_RELAY2") (class "Default")
      (node (ref "Q10") (pin "1") (pinfunction "G_1") (pintype "passive"))
      (node (ref "R8") (pin "2") (pinfunction "2_2") (pintype "passive"))
      (node (ref "U$4") (pin "2") (pinfunction "2_2") (pintype "passive"))
    )
    (net (code "57") (name "Net-(JP2-Pad1)") (class "Default")
      (node (ref "JP2") (pin "1") (pinfunction "1_1") (pintype "passive"))
      (node (ref "R1") (pin "2") (pinfunction "2_2") (pintype "passive"))
    )
    (net (code "58") (name "Net-(JP4-Pad1)") (class "Default")
      (node (ref "JP4") (pin "1") (pinfunction "1_1") (pintype "passive"))
      (node (ref "R4") (pin "2") (pinfunction "2_2") (pintype "passive"))
    )
    (net (code "59") (name "Net-(JP6-Pad1)") (class "Default")
      (node (ref "JP6") (pin "1") (pinfunction "1_1") (pintype "passive"))
      (node (ref "R2") (pin "2") (pinfunction "2_2") (pintype "passive"))
    )
    (net (code "60") (name "Net-(JP8-Pad1)") (class "Default")
      (node (ref "JP8") (pin "1") (pinfunction "1_1") (pintype "passive"))
      (node (ref "R3") (pin "2") (pinfunction "2_2") (pintype "passive"))
    )
    (net (code "61") (name "Net-(LED8-PadA)") (class "Default")
      (node (ref "LED8") (pin "A") (pinfunction "A_A") (pintype "passive"))
      (node (ref "R13") (pin "1") (pinfunction "1_1") (pintype "passive"))
    )
    (net (code "62") (name "Net-(LED9-PadA)") (class "Default")
      (node (ref "LED9") (pin "A") (pinfunction "A_A") (pintype "passive"))
      (node (ref "R20") (pin "1") (pinfunction "1_1") (pintype "passive"))
    )
    (net (code "63") (name "Net-(LED10-PadA)") (class "Default")
      (node (ref "LED10") (pin "A") (pinfunction "A_A") (pintype "passive"))
      (node (ref "R27") (pin "1") (pinfunction "1_1") (pintype "passive"))
    )
    (net (code "64") (name "Net-(LED11-PadA)") (class "Default")
      (node (ref "LED11") (pin "A") (pinfunction "A_A") (pintype "passive"))
      (node (ref "R34") (pin "1") (pinfunction "1_1") (pintype "passive"))
    )
    (net (code "65") (name "Net-(Q2-ANODE)") (class "Default")
      (node (ref "Q2") (pin "1") (pinfunction "ANODE_1") (pintype "passive"))
      (node (ref "R11") (pin "2") (pinfunction "2_2") (pintype "passive"))
    )
    (net (code "66") (name "Net-(Q3-PadB)") (class "Default")
      (node (ref "Q3") (pin "B") (pinfunction "B_B") (pintype "passive"))
      (node (ref "R12") (pin "2") (pinfunction "2_2") (pintype "passive"))
    )
    (net (code "67") (name "Net-(Q5-ANODE)") (class "Default")
      (node (ref "Q5") (pin "1") (pinfunction "ANODE_1") (pintype "passive"))
      (node (ref "R18") (pin "2") (pinfunction "2_2") (pintype "passive"))
    )
    (net (code "68") (name "Net-(Q6-PadB)") (class "Default")
      (node (ref "Q6") (pin "B") (pinfunction "B_B") (pintype "passive"))
      (node (ref "R19") (pin "2") (pinfunction "2_2") (pintype "passive"))
    )
    (net (code "69") (name "Net-(Q8-ANODE)") (class "Default")
      (node (ref "Q8") (pin "1") (pinfunction "ANODE_1") (pintype "passive"))
      (node (ref "R25") (pin "2") (pinfunction "2_2") (pintype "passive"))
    )
    (net (code "70") (name "Net-(Q9-PadB)") (class "Default")
      (node (ref "Q9") (pin "B") (pinfunction "B_B") (pintype "passive"))
      (node (ref "R26") (pin "2") (pinfunction "2_2") (pintype "passive"))
    )
    (net (code "71") (name "Net-(Q11-ANODE)") (class "Default")
      (node (ref "Q11") (pin "1") (pinfunction "ANODE_1") (pintype "passive"))
      (node (ref "R32") (pin "2") (pinfunction "2_2") (pintype "passive"))
    )
    (net (code "72") (name "Net-(Q12-PadB)") (class "Default")
      (node (ref "Q12") (pin "B") (pinfunction "B_B") (pintype "passive"))
      (node (ref "R33") (pin "2") (pinfunction "2_2") (pintype "passive"))
    )
    (net (code "73") (name "Net-(Q13-G)") (class "Default")
      (node (ref "13V_ZENER") (pin "A") (pinfunction "A_A") (pintype "passive"))
      (node (ref "Q13") (pin "1") (pinfunction "G_1") (pintype "passive"))
      (node (ref "R5") (pin "2") (pinfunction "2_2") (pintype "passive"))
    )
    (net (code "74") (name "Net-(Q14-G)") (class "Default")
      (node (ref "13V_ZENER1") (pin "A") (pinfunction "A_A") (pintype "passive"))
      (node (ref "Q14") (pin "1") (pinfunction "G_1") (pintype "passive"))
      (node (ref "R6") (pin "2") (pinfunction "2_2") (pintype "passive"))
    )
  )
)
